# KN_ATx32.net
KiCad netlist of a schematic drawn in Altium Designer
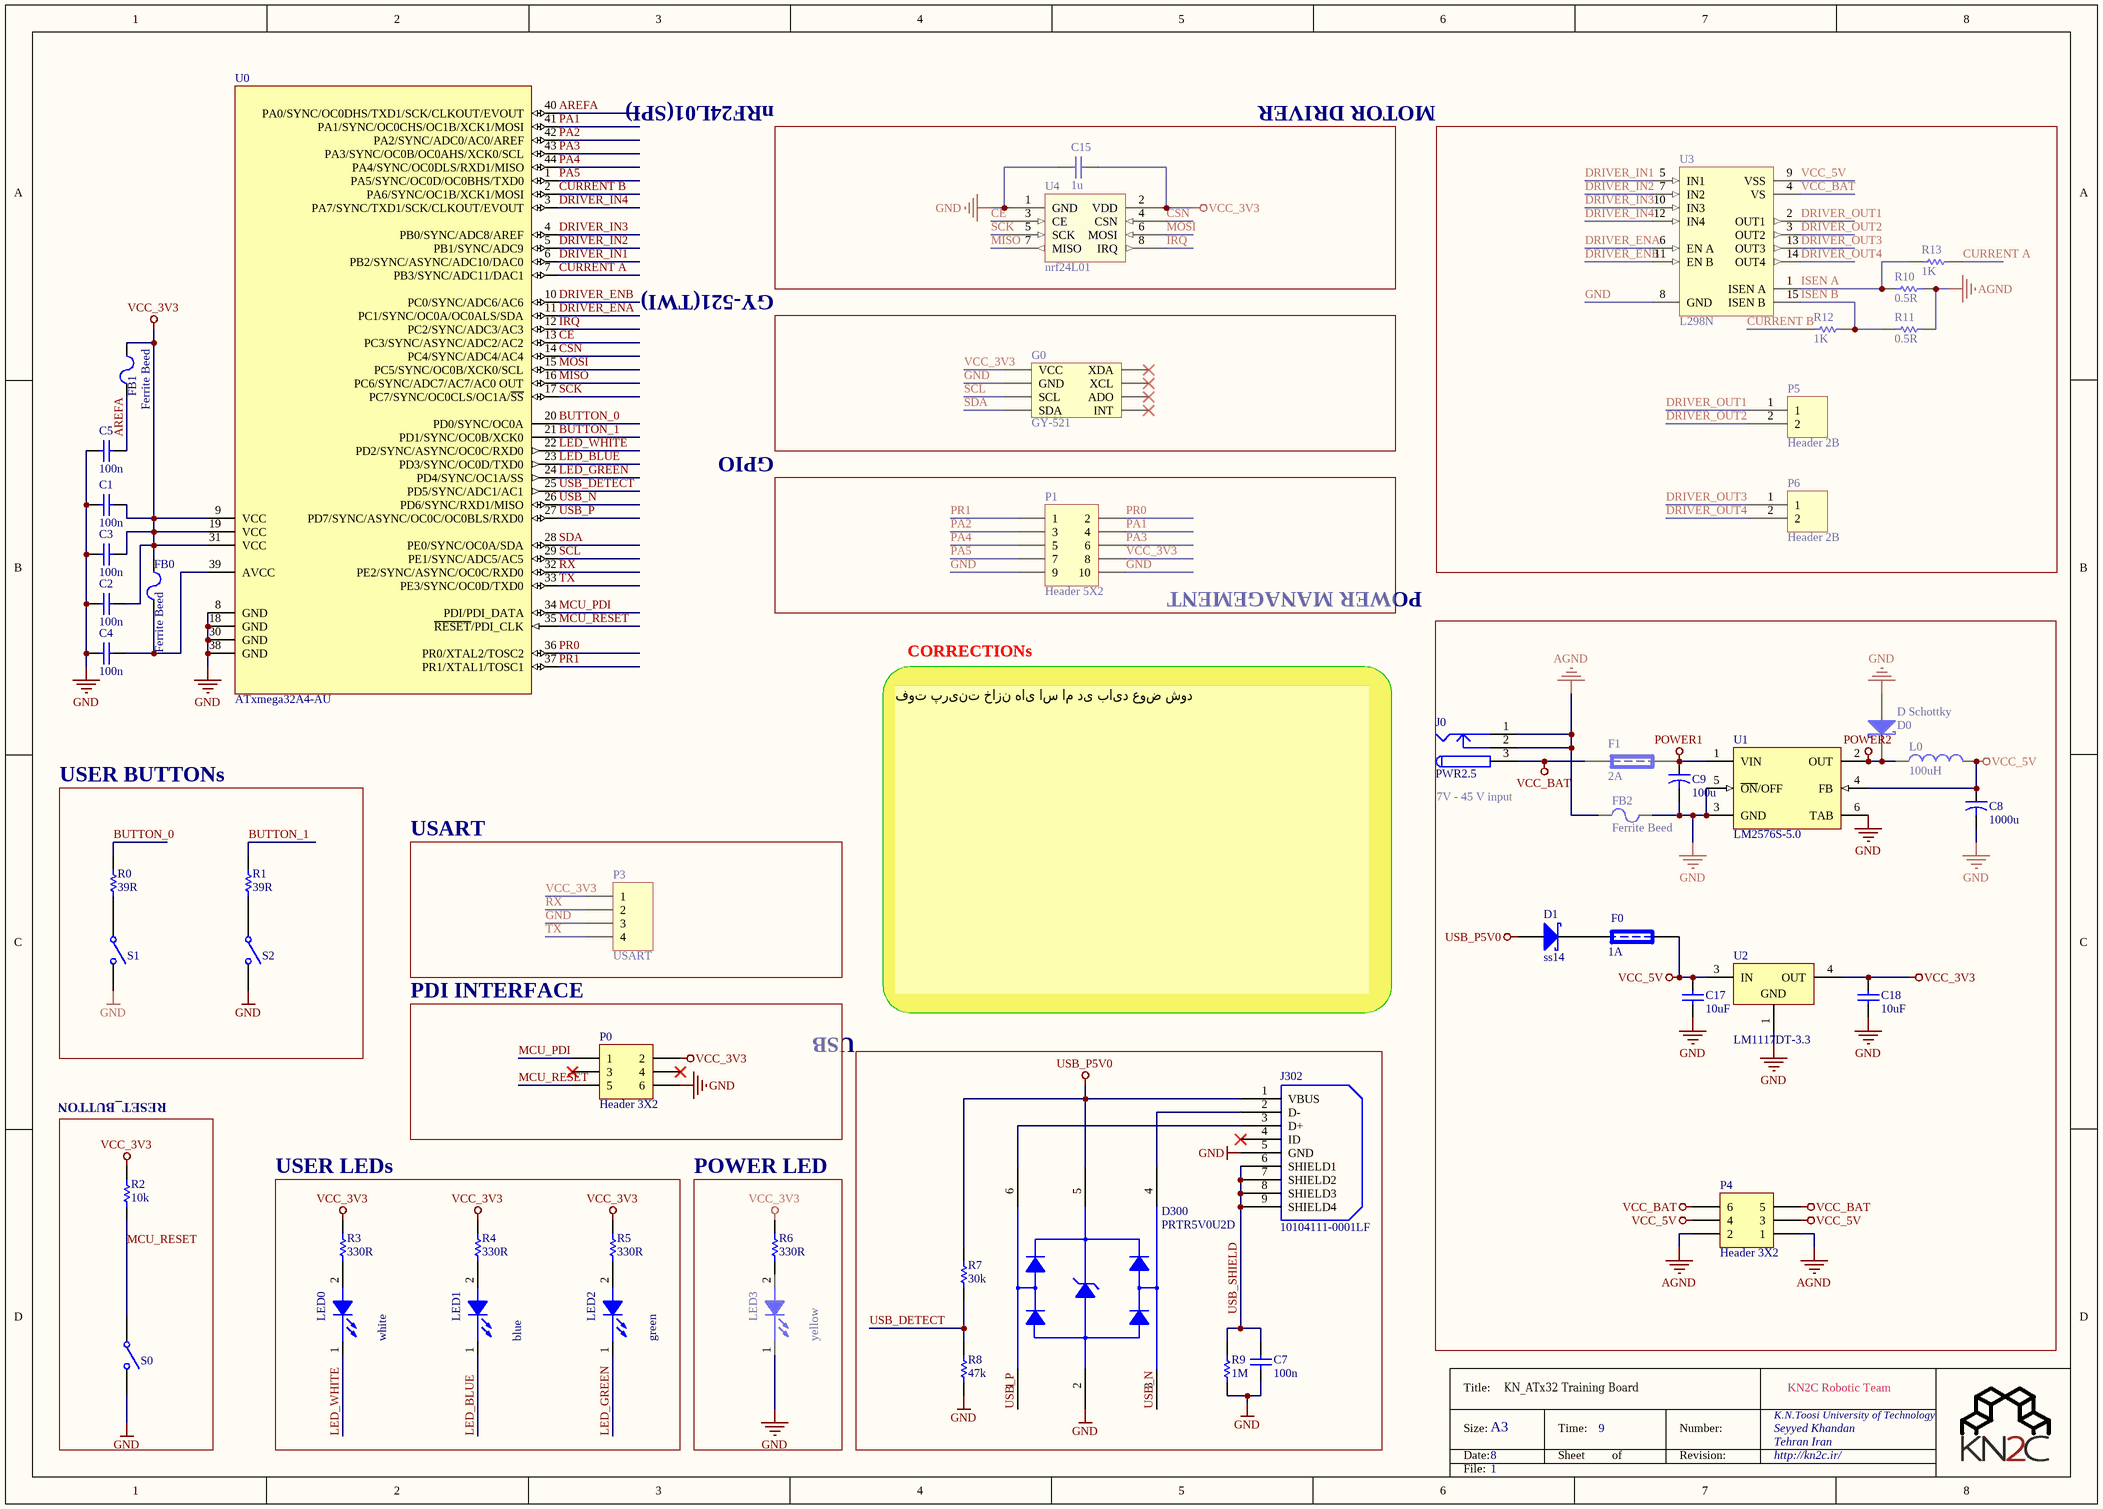
[diagram p0: KN_ATx32.SchDoc]

(export (version "E")
  (design (tool "Eeschema 10.0.6"))
  (components
    (comp (ref "C1")
      (value "100n")
      (footprint "6-0805_N")
      (description "Capacitor")
      (fields (field (name "PUBLISHER") "Altium Limited"))
      (libsource (lib "Miscellaneous Devices") (part "Cap"))
    )
    (comp (ref "C2")
      (value "100n")
      (footprint "6-0805_N")
      (description "Capacitor")
      (fields (field (name "PUBLISHER") "Altium Limited"))
      (libsource (lib "Miscellaneous Devices") (part "Cap"))
    )
    (comp (ref "C3")
      (value "100n")
      (footprint "6-0805_N")
      (description "Capacitor")
      (fields (field (name "PUBLISHER") "Altium Limited"))
      (libsource (lib "Miscellaneous Devices") (part "Cap"))
    )
    (comp (ref "C4")
      (value "100n")
      (footprint "6-0805_N")
      (description "Capacitor")
      (fields (field (name "PUBLISHER") "Altium Limited"))
      (libsource (lib "Miscellaneous Devices") (part "Cap"))
    )
    (comp (ref "C5")
      (value "100n")
      (footprint "6-0805_N")
      (description "Capacitor")
      (fields (field (name "PUBLISHER") "Altium Limited"))
      (libsource (lib "Miscellaneous Devices") (part "Cap"))
    )
    (comp (ref "C7")
      (value "100n")
      (footprint "6-0805_N")
      (description "Capacitor")
      (fields (field (name "PUBLISHER") "Altium Limited"))
      (libsource (lib "Miscellaneous Devices") (part "Cap"))
    )
    (comp (ref "C8")
      (value "1000u")
      (footprint "AP1-00122")
      (description "Capacitor")
      (fields (field (name "PUBLISHER") "Altium Limited"))
      (libsource (lib "KN2CLib") (part "Cap_El_200V"))
    )
    (comp (ref "C9")
      (value "100u")
      (footprint "AP1-00122")
      (description "Capacitor")
      (fields (field (name "PUBLISHER") "Altium Limited"))
      (libsource (lib "KN2CLib") (part "Cap_El_200V"))
    )
    (comp (ref "C15")
      (value "1u")
      (footprint "6-0805_N")
      (description "Capacitor")
      (fields (field (name "PUBLISHER") "Altium Limited"))
      (libsource (lib "Miscellaneous Devices") (part "Cap"))
    )
    (comp (ref "C17")
      (value "10uF")
      (footprint "2012[0805]")
      (description "Capacitor")
      (fields (field (name "PUBLISHER") "Altium Limited"))
      (libsource (lib "KN2CLib") (part "Cap_UP"))
    )
    (comp (ref "C18")
      (value "10uF")
      (footprint "2012[0805]")
      (description "Capacitor")
      (fields (field (name "PUBLISHER") "Altium Limited"))
      (libsource (lib "KN2CLib") (part "Cap_UP"))
    )
    (comp (ref "D0")
      (value "D Schottky")
      (footprint "us1m")
      (description "Schottky Diode")
      (fields (field (name "PUBLISHER") "Altium Limited"))
      (libsource (lib "Miscellaneous Devices") (part "D Schottky"))
    )
    (comp (ref "D1")
      (value "ss14")
      (footprint "US1m")
      (description "Schottky Diode")
      (fields (field (name "PUBLISHER") "Altium Limited"))
      (libsource (lib "Miscellaneous Devices") (part "D Schottky"))
    )
    (comp (ref "D300")
      (value "PRTR5V0U2D")
      (footprint "SOT457_N")
      (description "Double rail-to-rail USB ESD protection diode")
      (fields (field (name "MANUFACTURER") "Philips") (field (name "MPN") "PRTR5V0U2X"))
      (libsource (lib "KN2CLib") (part "PRTR5V0U2D"))
    )
    (comp (ref "F0")
      (value "1A")
      (footprint "1206")
      (description "Fuse")
      (fields (field (name "PUBLISHER") "Altium Limited"))
      (libsource (lib "KN2CLib") (part "Fuse"))
    )
    (comp (ref "F1")
      (value "2A")
      (footprint "1206")
      (description "Fuse")
      (fields (field (name "PUBLISHER") "Altium Limited"))
      (libsource (lib "KN2CLib") (part "Fuse"))
    )
    (comp (ref "FB0")
      (value "Ferrite Beed")
      (footprint "2012[0805]")
      (fields (field (name "PUBLISHER") "Altium Limited"))
      (libsource (lib "KN2CLib") (part "Ferrite Beed"))
    )
    (comp (ref "FB1")
      (value "Ferrite Beed")
      (footprint "2012[0805]")
      (fields (field (name "PUBLISHER") "Altium Limited"))
      (libsource (lib "KN2CLib") (part "Ferrite Beed"))
    )
    (comp (ref "FB2")
      (value "Ferrite Beed")
      (footprint "AXIAL-0.3")
      (fields (field (name "PUBLISHER") "Altium Limited"))
      (libsource (lib "KN2CLib") (part "Ferrite Beed"))
    )
    (comp (ref "G0") (value "GY-521") (footprint "GY-521") (libsource (lib "KN2CLib") (part "GY-521")))
    (comp (ref "J0")
      (value "PWR2.5")
      (footprint "CHARGER2")
      (description "Low Voltage Power Supply Connector")
      (fields (field (name "PUBLISHER") "Altium Limited"))
      (libsource (lib "KN2CLib") (part "PWR2.5"))
    )
    (comp (ref "J302")
      (value "10104111-0001LF")
      (footprint "AP8-00852")
      (description "Micro USB AB Connector")
      (fields (field (name "MANUFACTURER") "FCI") (field (name "Comment") "USB_AB"))
      (libsource (lib "KN2CLib") (part "USB_AB"))
    )
    (comp (ref "L0")
      (value "100uH")
      (footprint "INDUCTOR_SMD")
      (description "Inductor")
      (fields (field (name "PUBLISHER") "Altium Limited"))
      (libsource (lib "KN2CLib") (part "Inductor"))
    )
    (comp (ref "LED0")
      (value "white")
      (footprint "6-0805_N")
      (description "LED, Yellow, Wave length=591nm, SMD 0805, ±70°")
      (fields (field (name "MANUFACTURER") "Everlight") (field (name "MPN") "17-21UYC/S530-A3/TR8"))
      (libsource (lib "AltiumDbLib") (part "LED_12"))
    )
    (comp (ref "LED1")
      (value "blue")
      (footprint "6-0805_N")
      (description "LED, Yellow, Wave length=591nm, SMD 0805, ±70°")
      (fields (field (name "MANUFACTURER") "Everlight") (field (name "MPN") "17-21UYC/S530-A3/TR8"))
      (libsource (lib "AltiumDbLib") (part "LED_12"))
    )
    (comp (ref "LED2")
      (value "green")
      (footprint "6-0805_N")
      (description "LED, Yellow, Wave length=591nm, SMD 0805, ±70°")
      (fields (field (name "MANUFACTURER") "Everlight") (field (name "MPN") "17-21UYC/S530-A3/TR8"))
      (libsource (lib "AltiumDbLib") (part "LED_12"))
    )
    (comp (ref "LED3")
      (value "yellow")
      (footprint "6-0805_N")
      (description "LED, Yellow, Wave length=591nm, SMD 0805, ±70°")
      (fields (field (name "MANUFACTURER") "Everlight") (field (name "MPN") "17-21UYC/S530-A3/TR8"))
      (libsource (lib "AltiumDbLib") (part "LED_12"))
    )
    (comp (ref "P0")
      (value "Header 3X2")
      (footprint "HDRBOX2X3")
      (description "Header, 3-Pin, Dual row")
      (fields (field (name "PUBLISHER") "Altium Limited"))
      (libsource (lib "KN2CLib") (part "Header 3X2"))
    )
    (comp (ref "P1")
      (value "Header 5X2")
      (footprint "HDR2X5")
      (description "Header, 5-Pin, Dual row")
      (fields (field (name "PUBLISHER") "Altium Limited"))
      (libsource (lib "KN2CLib") (part "Header 5X2"))
    )
    (comp (ref "P3")
      (value "USART")
      (footprint "HDR1X4")
      (description "Header, 4-Pin")
      (fields (field (name "PUBLISHER") "Altium Limited"))
      (libsource (lib "Miscellaneous Connectors") (part "Header 4"))
    )
    (comp (ref "P4")
      (value "Header 3X2")
      (footprint "HDR2X3")
      (description "Header, 3-Pin, Dual row")
      (fields (field (name "PUBLISHER") "Altium Limited"))
      (libsource (lib "") (part "Header 3X2_1"))
    )
    (comp (ref "P5") (value "Header 2B") (footprint "CON2") (libsource (lib "KN2CLib") (part "Header 2B")))
    (comp (ref "P6") (value "Header 2B") (footprint "CON2") (libsource (lib "KN2CLib") (part "Header 2B")))
    (comp (ref "R0")
      (value "39R")
      (footprint "2012[0805]")
      (description "Semiconductor Resistor")
      (fields (field (name "PUBLISHER") "Altium Limited"))
      (libsource (lib "KN2CLib") (part "Res"))
    )
    (comp (ref "R1")
      (value "39R")
      (footprint "2012[0805]")
      (description "Semiconductor Resistor")
      (fields (field (name "PUBLISHER") "Altium Limited"))
      (libsource (lib "KN2CLib") (part "Res"))
    )
    (comp (ref "R2")
      (value "10k")
      (footprint "2012[0805]")
      (description "Semiconductor Resistor")
      (fields (field (name "PUBLISHER") "Altium Limited"))
      (libsource (lib "KN2CLib") (part "Res"))
    )
    (comp (ref "R3")
      (value "330R")
      (footprint "2012[0805]")
      (description "Semiconductor Resistor")
      (fields (field (name "PUBLISHER") "Altium Limited"))
      (libsource (lib "KN2CLib") (part "Res"))
    )
    (comp (ref "R4")
      (value "330R")
      (footprint "2012[0805]")
      (description "Semiconductor Resistor")
      (fields (field (name "PUBLISHER") "Altium Limited"))
      (libsource (lib "KN2CLib") (part "Res"))
    )
    (comp (ref "R5")
      (value "330R")
      (footprint "2012[0805]")
      (description "Semiconductor Resistor")
      (fields (field (name "PUBLISHER") "Altium Limited"))
      (libsource (lib "KN2CLib") (part "Res"))
    )
    (comp (ref "R6")
      (value "330R")
      (footprint "2012[0805]")
      (description "Semiconductor Resistor")
      (fields (field (name "PUBLISHER") "Altium Limited"))
      (libsource (lib "KN2CLib") (part "Res"))
    )
    (comp (ref "R7")
      (value "30k")
      (footprint "2012[0805]")
      (description "Semiconductor Resistor")
      (fields (field (name "PUBLISHER") "Altium Limited"))
      (libsource (lib "KN2CLib") (part "Res"))
    )
    (comp (ref "R8")
      (value "47k")
      (footprint "2012[0805]")
      (description "Semiconductor Resistor")
      (fields (field (name "PUBLISHER") "Altium Limited"))
      (libsource (lib "KN2CLib") (part "Res"))
    )
    (comp (ref "R9")
      (value "1M")
      (footprint "2012[0805]")
      (description "Semiconductor Resistor")
      (fields (field (name "PUBLISHER") "Altium Limited"))
      (libsource (lib "KN2CLib") (part "Res"))
    )
    (comp (ref "R10")
      (value "0.5R")
      (footprint "6332[2512]")
      (description "Semiconductor Resistor")
      (fields (field (name "PUBLISHER") "Altium Limited"))
      (libsource (lib "KN2CLib") (part "Res"))
    )
    (comp (ref "R11")
      (value "0.5R")
      (footprint "6332[2512]")
      (description "Semiconductor Resistor")
      (fields (field (name "PUBLISHER") "Altium Limited"))
      (libsource (lib "KN2CLib") (part "Res"))
    )
    (comp (ref "R12")
      (value "1K")
      (footprint "2012[0805]")
      (description "Semiconductor Resistor")
      (fields (field (name "PUBLISHER") "Altium Limited"))
      (libsource (lib "KN2CLib") (part "Res"))
    )
    (comp (ref "R13")
      (value "1K")
      (footprint "2012[0805]")
      (description "Semiconductor Resistor")
      (fields (field (name "PUBLISHER") "Altium Limited"))
      (libsource (lib "KN2CLib") (part "Res"))
    )
    (comp (ref "S0")
      (value "SW-SPST")
      (footprint "pushbutton_smd")
      (description "Single-Pole, Single-Throw Switch")
      (fields (field (name "PUBLISHER") "Altium Limited"))
      (libsource (lib "KN2CLib") (part "SW-SPST"))
    )
    (comp (ref "S1")
      (value "SW-SPST")
      (footprint "pushbutton_smd")
      (description "Single-Pole, Single-Throw Switch")
      (fields (field (name "PUBLISHER") "Altium Limited"))
      (libsource (lib "KN2CLib") (part "SW-SPST"))
    )
    (comp (ref "S2")
      (value "SW-SPST")
      (footprint "pushbutton_smd")
      (description "Single-Pole, Single-Throw Switch")
      (fields (field (name "PUBLISHER") "Altium Limited"))
      (libsource (lib "KN2CLib") (part "SW-SPST"))
    )
    (comp (ref "U0")
      (value "ATxmega32A4-AU")
      (footprint "44A_N")
      (fields (field (name "PUBLISHER") "Altium Limited"))
      (libsource (lib "Atmel Microcontroller 8-16-Bit AVR XMEGA") (part "ATxmega32A4-AU"))
    )
    (comp (ref "U1")
      (value "LM2576S-5.0")
      (footprint "TS5B_N")
      (description "SIMPLE SWITCHER® 3A Step-Down Voltage Regulator, 5-pin TO-263")
      (fields
        (field (name "MANUFACTURER") "National Semiconductor")
        (field (name "PUBLISHER") "Altium Limited")
      )
      (libsource (lib "KN2CLib") (part "LM2576S-5.0"))
    )
    (comp (ref "U2")
      (value "LM1117DT-3.3")
      (footprint "SOT223")
      (description "800mA Low-Dropout Linear Regulator, 3-pin TO-252")
      (fields
        (field (name "MANUFACTURER") "National Semiconductor")
        (field (name "PUBLISHER") "Altium Limited")
      )
      (libsource (lib "NSC LDO") (part "LM1117DT-3.3"))
    )
    (comp (ref "U3")
      (value "L298N")
      (footprint "Multiwatt15V")
      (description "Dual Full Bridge Driver")
      (fields (field (name "PUBLISHER") "Altium Limited"))
      (libsource (lib "ST Interface DC Motor Controller") (part "L298N"))
    )
    (comp (ref "U4") (value "nrf24L01") (footprint "NRF24L01") (libsource (lib "KN2CLib") (part "nrf24L01")))
  )
  (nets
    (net (code "1") (name "/AREFA") (class "Default")
      (node (ref "C5") (pin "2") (pinfunction "2_2") (pintype "passive"))
      (node (ref "FB1") (pin "1") (pinfunction "1_1") (pintype "passive"))
      (node (ref "U0") (pin "40") (pinfunction "PA0/SYNC/OC0DHS/TXD1/SCK/CLKOUT/EVOUT_40") (pintype "bidirectional"))
    )
    (net (code "2") (name "/BUTTON_0") (class "Default")
      (node (ref "R0") (pin "2") (pinfunction "2_2") (pintype "passive"))
      (node (ref "U0") (pin "20") (pinfunction "PD0/SYNC/OC0A_20") (pintype "open_emitter"))
    )
    (net (code "3") (name "/BUTTON_1") (class "Default")
      (node (ref "R1") (pin "2") (pinfunction "2_2") (pintype "passive"))
      (node (ref "U0") (pin "21") (pinfunction "PD1/SYNC/OC0B/XCK0_21") (pintype "open_emitter"))
    )
    (net (code "4") (name "/CE") (class "Default")
      (node (ref "U0") (pin "13") (pinfunction "PC3/SYNC/ASYNC/ADC2/AC2_13") (pintype "bidirectional"))
      (node (ref "U4") (pin "3") (pinfunction "CE_3") (pintype "input"))
    )
    (net (code "5") (name "/CSN") (class "Default")
      (node (ref "U0") (pin "14") (pinfunction "PC4/SYNC/ADC4/AC4_14") (pintype "bidirectional"))
      (node (ref "U4") (pin "4") (pinfunction "CSN_4") (pintype "input"))
    )
    (net (code "6") (name "/CURRENT A") (class "Default")
      (node (ref "R13") (pin "2") (pinfunction "2_2") (pintype "passive"))
      (node (ref "U0") (pin "7") (pinfunction "PB3/SYNC/ADC11/DAC1_7") (pintype "bidirectional"))
    )
    (net (code "7") (name "/CURRENT B") (class "Default")
      (node (ref "R12") (pin "1") (pinfunction "1_1") (pintype "passive"))
      (node (ref "U0") (pin "2") (pinfunction "PA6/SYNC/OC1B/XCK1/MOSI_2") (pintype "bidirectional"))
    )
    (net (code "8") (name "/DRIVER_ENA") (class "Default")
      (node (ref "U0") (pin "11") (pinfunction "PC1/SYNC/OC0A/OC0ALS/SDA_11") (pintype "bidirectional"))
      (node (ref "U3") (pin "6") (pinfunction "EN_A_6") (pintype "input"))
    )
    (net (code "9") (name "/DRIVER_ENB") (class "Default")
      (node (ref "U0") (pin "10") (pinfunction "PC0/SYNC/ADC6/AC6_10") (pintype "bidirectional"))
      (node (ref "U3") (pin "11") (pinfunction "EN_B_11") (pintype "input"))
    )
    (net (code "10") (name "/DRIVER_IN1") (class "Default")
      (node (ref "U0") (pin "6") (pinfunction "PB2/SYNC/ASYNC/ADC10/DAC0_6") (pintype "bidirectional"))
      (node (ref "U3") (pin "5") (pinfunction "IN1_5") (pintype "input"))
    )
    (net (code "11") (name "/DRIVER_IN2") (class "Default")
      (node (ref "U0") (pin "5") (pinfunction "PB1/SYNC/ADC9_5") (pintype "bidirectional"))
      (node (ref "U3") (pin "7") (pinfunction "IN2_7") (pintype "input"))
    )
    (net (code "12") (name "/DRIVER_IN3") (class "Default")
      (node (ref "U0") (pin "4") (pinfunction "PB0/SYNC/ADC8/AREF_4") (pintype "bidirectional"))
      (node (ref "U3") (pin "10") (pinfunction "IN3_10") (pintype "input"))
    )
    (net (code "13") (name "/DRIVER_IN4") (class "Default")
      (node (ref "U0") (pin "3") (pinfunction "PA7/SYNC/TXD1/SCK/CLKOUT/EVOUT_3") (pintype "bidirectional"))
      (node (ref "U3") (pin "12") (pinfunction "IN4_12") (pintype "input"))
    )
    (net (code "14") (name "/DRIVER_OUT1") (class "Default")
      (node (ref "P5") (pin "1") (pinfunction "1_1") (pintype "passive"))
      (node (ref "U3") (pin "2") (pinfunction "OUT1_2") (pintype "output"))
    )
    (net (code "15") (name "/DRIVER_OUT2") (class "Default")
      (node (ref "P5") (pin "2") (pinfunction "2_2") (pintype "passive"))
      (node (ref "U3") (pin "3") (pinfunction "OUT2_3") (pintype "output"))
    )
    (net (code "16") (name "/DRIVER_OUT3") (class "Default")
      (node (ref "P6") (pin "1") (pinfunction "1_1") (pintype "passive"))
      (node (ref "U3") (pin "13") (pinfunction "OUT3_13") (pintype "output"))
    )
    (net (code "17") (name "/DRIVER_OUT4") (class "Default")
      (node (ref "P6") (pin "2") (pinfunction "2_2") (pintype "passive"))
      (node (ref "U3") (pin "14") (pinfunction "OUT4_14") (pintype "output"))
    )
    (net (code "18") (name "/IRQ") (class "Default")
      (node (ref "U0") (pin "12") (pinfunction "PC2/SYNC/ADC3/AC3_12") (pintype "bidirectional"))
      (node (ref "U4") (pin "8") (pinfunction "IRQ_8") (pintype "output"))
    )
    (net (code "19") (name "/ISEN A") (class "Default")
      (node (ref "R10") (pin "1") (pinfunction "1_1") (pintype "passive"))
      (node (ref "R13") (pin "1") (pinfunction "1_1") (pintype "passive"))
      (node (ref "U3") (pin "1") (pinfunction "ISEN_A_1") (pintype "passive"))
    )
    (net (code "20") (name "/ISEN B") (class "Default")
      (node (ref "R11") (pin "1") (pinfunction "1_1") (pintype "passive"))
      (node (ref "R12") (pin "2") (pinfunction "2_2") (pintype "passive"))
      (node (ref "U3") (pin "15") (pinfunction "ISEN_B_15") (pintype "passive"))
    )
    (net (code "21") (name "/LED_BLUE") (class "Default")
      (node (ref "LED1") (pin "1") (pinfunction "CATHODE_1") (pintype "passive"))
      (node (ref "U0") (pin "23") (pinfunction "PD3/SYNC/OC0D/TXD0_23") (pintype "output"))
    )
    (net (code "22") (name "/LED_GREEN") (class "Default")
      (node (ref "LED2") (pin "1") (pinfunction "CATHODE_1") (pintype "passive"))
      (node (ref "U0") (pin "24") (pinfunction "PD4/SYNC/OC1A/SS_24") (pintype "output"))
    )
    (net (code "23") (name "/LED_WHITE") (class "Default")
      (node (ref "LED0") (pin "1") (pinfunction "CATHODE_1") (pintype "passive"))
      (node (ref "U0") (pin "22") (pinfunction "PD2/SYNC/ASYNC/OC0C/RXD0_22") (pintype "output"))
    )
    (net (code "24") (name "/MCU_PDI") (class "Default")
      (node (ref "P0") (pin "1") (pinfunction "1_1") (pintype "passive"))
      (node (ref "U0") (pin "34") (pinfunction "PDI/PDI_DATA_34") (pintype "bidirectional"))
    )
    (net (code "25") (name "/MCU_RESET") (class "Default")
      (node (ref "P0") (pin "5") (pinfunction "5_5") (pintype "passive"))
      (node (ref "R2") (pin "1") (pinfunction "1_1") (pintype "passive"))
      (node (ref "S0") (pin "1") (pinfunction "COMMON_1") (pintype "passive"))
      (node (ref "U0") (pin "35") (pinfunction "~{RESET}/PDI_CLK_35") (pintype "input"))
    )
    (net (code "26") (name "/MISO") (class "Default")
      (node (ref "U0") (pin "16") (pinfunction "PC6/SYNC/ADC7/AC7/AC0_OUT_16") (pintype "bidirectional"))
      (node (ref "U4") (pin "7") (pinfunction "MISO_7") (pintype "output"))
    )
    (net (code "27") (name "/MOSI") (class "Default")
      (node (ref "U0") (pin "15") (pinfunction "PC5/SYNC/OC0B/XCK0/SCL_15") (pintype "bidirectional"))
      (node (ref "U4") (pin "6") (pinfunction "MOSI_6") (pintype "input"))
    )
    (net (code "28") (name "/PA1") (class "Default")
      (node (ref "P1") (pin "4") (pinfunction "4_4") (pintype "passive"))
      (node (ref "U0") (pin "41") (pinfunction "PA1/SYNC/OC0CHS/OC1B/XCK1/MOSI_41") (pintype "bidirectional"))
    )
    (net (code "29") (name "/PA2") (class "Default")
      (node (ref "P1") (pin "3") (pinfunction "3_3") (pintype "passive"))
      (node (ref "U0") (pin "42") (pinfunction "PA2/SYNC/ADC0/AC0/AREF_42") (pintype "bidirectional"))
    )
    (net (code "30") (name "/PA3") (class "Default")
      (node (ref "P1") (pin "6") (pinfunction "6_6") (pintype "passive"))
      (node (ref "U0") (pin "43") (pinfunction "PA3/SYNC/OC0B/OC0AHS/XCK0/SCL_43") (pintype "bidirectional"))
    )
    (net (code "31") (name "/PA4") (class "Default")
      (node (ref "P1") (pin "5") (pinfunction "5_5") (pintype "passive"))
      (node (ref "U0") (pin "44") (pinfunction "PA4/SYNC/OC0DLS/RXD1/MISO_44") (pintype "bidirectional"))
    )
    (net (code "32") (name "/PA5") (class "Default")
      (node (ref "P1") (pin "7") (pinfunction "7_7") (pintype "passive"))
      (node (ref "U0") (pin "1") (pinfunction "PA5/SYNC/OC0D/OC0BHS/TXD0_1") (pintype "bidirectional"))
    )
    (net (code "33") (name "/PR0") (class "Default")
      (node (ref "P1") (pin "2") (pinfunction "2_2") (pintype "passive"))
      (node (ref "U0") (pin "36") (pinfunction "PR0/XTAL2/TOSC2_36") (pintype "bidirectional"))
    )
    (net (code "34") (name "/PR1") (class "Default")
      (node (ref "P1") (pin "1") (pinfunction "1_1") (pintype "passive"))
      (node (ref "U0") (pin "37") (pinfunction "PR1/XTAL1/TOSC1_37") (pintype "bidirectional"))
    )
    (net (code "35") (name "/RX") (class "Default")
      (node (ref "P3") (pin "2") (pinfunction "2_2") (pintype "passive"))
      (node (ref "U0") (pin "32") (pinfunction "PE2/SYNC/ASYNC/OC0C/RXD0_32") (pintype "bidirectional"))
    )
    (net (code "36") (name "/SCK") (class "Default")
      (node (ref "U0") (pin "17") (pinfunction "PC7/SYNC/OC0CLS/OC1A/~{SS}_17") (pintype "bidirectional"))
      (node (ref "U4") (pin "5") (pinfunction "SCK_5") (pintype "input"))
    )
    (net (code "37") (name "/SCL") (class "Default")
      (node (ref "G0") (pin "3") (pinfunction "SCL_3") (pintype "passive"))
      (node (ref "U0") (pin "29") (pinfunction "PE1/SYNC/ADC5/AC5_29") (pintype "bidirectional"))
    )
    (net (code "38") (name "/SDA") (class "Default")
      (node (ref "G0") (pin "4") (pinfunction "SDA_4") (pintype "passive"))
      (node (ref "U0") (pin "28") (pinfunction "PE0/SYNC/OC0A/SDA_28") (pintype "bidirectional"))
    )
    (net (code "39") (name "/TX") (class "Default")
      (node (ref "P3") (pin "4") (pinfunction "4_4") (pintype "passive"))
      (node (ref "U0") (pin "33") (pinfunction "PE3/SYNC/OC0D/TXD0_33") (pintype "bidirectional"))
    )
    (net (code "40") (name "/USB_DETECT") (class "Default")
      (node (ref "R7") (pin "1") (pinfunction "1_1") (pintype "passive"))
      (node (ref "R8") (pin "2") (pinfunction "2_2") (pintype "passive"))
      (node (ref "U0") (pin "25") (pinfunction "PD5/SYNC/ADC1/AC1_25") (pintype "output"))
    )
    (net (code "41") (name "/USB_N") (class "Default")
      (node (ref "D300") (pin "3") (pinfunction "I/O2_3") (pintype "passive"))
      (node (ref "U0") (pin "26") (pinfunction "PD6/SYNC/RXD1/MISO_26") (pintype "bidirectional"))
    )
    (net (code "42") (name "/USB_P") (class "Default")
      (node (ref "D300") (pin "1") (pinfunction "I/O_1_1") (pintype "passive"))
      (node (ref "U0") (pin "27") (pinfunction "PD7/SYNC/ASYNC/OC0C/OC0BLS/RXD0_27") (pintype "bidirectional"))
    )
    (net (code "43") (name "/USB_SHIELD") (class "Default")
      (node (ref "C7") (pin "2") (pinfunction "2_2") (pintype "passive"))
      (node (ref "J302") (pin "6") (pinfunction "SHIELD1_6") (pintype "passive"))
      (node (ref "J302") (pin "7") (pinfunction "SHIELD2_7") (pintype "passive"))
      (node (ref "J302") (pin "8") (pinfunction "SHIELD3_8") (pintype "passive"))
      (node (ref "J302") (pin "9") (pinfunction "SHIELD4_9") (pintype "passive"))
      (node (ref "R9") (pin "2") (pinfunction "2_2") (pintype "passive"))
    )
    (net (code "44") (name "AGND") (class "Default")
      (node (ref "FB2") (pin "2") (pinfunction "2_2") (pintype "passive"))
      (node (ref "J0") (pin "1") (pinfunction "1_1") (pintype "passive"))
      (node (ref "J0") (pin "2") (pinfunction "2_2") (pintype "passive"))
      (node (ref "P4") (pin "1") (pinfunction "1_1") (pintype "passive"))
      (node (ref "P4") (pin "2") (pinfunction "2_2") (pintype "passive"))
      (node (ref "R10") (pin "2") (pinfunction "2_2") (pintype "passive"))
      (node (ref "R11") (pin "2") (pinfunction "2_2") (pintype "passive"))
    )
    (net (code "45") (name "GND") (class "Default")
      (node (ref "C1") (pin "1") (pinfunction "1_1") (pintype "passive"))
      (node (ref "C15") (pin "1") (pinfunction "1_1") (pintype "passive"))
      (node (ref "C17") (pin "1") (pinfunction "1_1") (pintype "passive"))
      (node (ref "C18") (pin "1") (pinfunction "1_1") (pintype "passive"))
      (node (ref "C2") (pin "1") (pinfunction "1_1") (pintype "passive"))
      (node (ref "C3") (pin "1") (pinfunction "1_1") (pintype "passive"))
      (node (ref "C4") (pin "1") (pinfunction "1_1") (pintype "passive"))
      (node (ref "C5") (pin "1") (pinfunction "1_1") (pintype "passive"))
      (node (ref "C7") (pin "1") (pinfunction "1_1") (pintype "passive"))
      (node (ref "C8") (pin "2") (pinfunction "2_2") (pintype "passive"))
      (node (ref "C9") (pin "2") (pinfunction "2_2") (pintype "passive"))
      (node (ref "D0") (pin "1") (pinfunction "A_1") (pintype "passive"))
      (node (ref "D300") (pin "2") (pinfunction "GND_2") (pintype "passive"))
      (node (ref "FB2") (pin "1") (pinfunction "1_1") (pintype "passive"))
      (node (ref "G0") (pin "2") (pinfunction "GND_2") (pintype "passive"))
      (node (ref "J302") (pin "5") (pinfunction "GND_5") (pintype "passive"))
      (node (ref "LED3") (pin "1") (pinfunction "CATHODE_1") (pintype "passive"))
      (node (ref "P0") (pin "6") (pinfunction "6_6") (pintype "passive"))
      (node (ref "P1") (pin "10") (pinfunction "10_10") (pintype "passive"))
      (node (ref "P1") (pin "9") (pinfunction "9_9") (pintype "passive"))
      (node (ref "P3") (pin "3") (pinfunction "3_3") (pintype "passive"))
      (node (ref "R8") (pin "1") (pinfunction "1_1") (pintype "passive"))
      (node (ref "R9") (pin "1") (pinfunction "1_1") (pintype "passive"))
      (node (ref "S0") (pin "2") (pinfunction "NO_2") (pintype "passive"))
      (node (ref "S1") (pin "2") (pinfunction "NO_2") (pintype "passive"))
      (node (ref "S2") (pin "2") (pinfunction "NO_2") (pintype "passive"))
      (node (ref "U0") (pin "18") (pinfunction "GND_18") (pintype "power_in"))
      (node (ref "U0") (pin "30") (pinfunction "GND_30") (pintype "power_in"))
      (node (ref "U0") (pin "38") (pinfunction "GND_38") (pintype "power_in"))
      (node (ref "U0") (pin "8") (pinfunction "GND_8") (pintype "power_in"))
      (node (ref "U1") (pin "3") (pinfunction "GND_3") (pintype "power_in"))
      (node (ref "U1") (pin "5") (pinfunction "~{ON}/OFF_5") (pintype "input"))
      (node (ref "U1") (pin "6") (pinfunction "TAB_6") (pintype "power_in"))
      (node (ref "U2") (pin "1") (pinfunction "GND_1") (pintype "power_in"))
      (node (ref "U3") (pin "8") (pinfunction "GND_8") (pintype "power_in"))
      (node (ref "U4") (pin "1") (pinfunction "GND_1") (pintype "power_in"))
    )
    (net (code "46") (name "Net-(D1-K)") (class "Default")
      (node (ref "D1") (pin "2") (pinfunction "K_2") (pintype "passive"))
      (node (ref "F0") (pin "2") (pinfunction "2_2") (pintype "passive"))
    )
    (net (code "47") (name "Net-(D300-I{slash}O1)") (class "Default")
      (node (ref "D300") (pin "6") (pinfunction "I/O1_6") (pintype "passive"))
      (node (ref "J302") (pin "3") (pinfunction "D+_3") (pintype "passive"))
    )
    (net (code "48") (name "Net-(J302-D-)") (class "Default")
      (node (ref "D300") (pin "4") (pinfunction "I/O2_4") (pintype "passive"))
      (node (ref "J302") (pin "2") (pinfunction "D-_2") (pintype "passive"))
    )
    (net (code "49") (name "Net-(LED0-ANODE)") (class "Default")
      (node (ref "LED0") (pin "2") (pinfunction "ANODE_2") (pintype "passive"))
      (node (ref "R3") (pin "1") (pinfunction "1_1") (pintype "passive"))
    )
    (net (code "50") (name "Net-(LED1-ANODE)") (class "Default")
      (node (ref "LED1") (pin "2") (pinfunction "ANODE_2") (pintype "passive"))
      (node (ref "R4") (pin "1") (pinfunction "1_1") (pintype "passive"))
    )
    (net (code "51") (name "Net-(LED2-ANODE)") (class "Default")
      (node (ref "LED2") (pin "2") (pinfunction "ANODE_2") (pintype "passive"))
      (node (ref "R5") (pin "1") (pinfunction "1_1") (pintype "passive"))
    )
    (net (code "52") (name "Net-(LED3-ANODE)") (class "Default")
      (node (ref "LED3") (pin "2") (pinfunction "ANODE_2") (pintype "passive"))
      (node (ref "R6") (pin "1") (pinfunction "1_1") (pintype "passive"))
    )
    (net (code "53") (name "Net-(S1-COMMON)") (class "Default")
      (node (ref "R0") (pin "1") (pinfunction "1_1") (pintype "passive"))
      (node (ref "S1") (pin "1") (pinfunction "COMMON_1") (pintype "passive"))
    )
    (net (code "54") (name "Net-(S2-COMMON)") (class "Default")
      (node (ref "R1") (pin "1") (pinfunction "1_1") (pintype "passive"))
      (node (ref "S2") (pin "1") (pinfunction "COMMON_1") (pintype "passive"))
    )
    (net (code "55") (name "Net-(U0-AVCC)") (class "Default")
      (node (ref "C4") (pin "2") (pinfunction "2_2") (pintype "passive"))
      (node (ref "FB0") (pin "1") (pinfunction "1_1") (pintype "passive"))
      (node (ref "U0") (pin "39") (pinfunction "AVCC_39") (pintype "power_in"))
    )
    (net (code "56") (name "POWER1") (class "Default")
      (node (ref "C9") (pin "1") (pinfunction "1_1") (pintype "passive"))
      (node (ref "F1") (pin "2") (pinfunction "2_2") (pintype "passive"))
      (node (ref "U1") (pin "1") (pinfunction "VIN_1") (pintype "power_in"))
    )
    (net (code "57") (name "POWER2") (class "Default")
      (node (ref "D0") (pin "2") (pinfunction "K_2") (pintype "passive"))
      (node (ref "L0") (pin "1") (pinfunction "1_1") (pintype "passive"))
      (node (ref "U1") (pin "2") (pinfunction "OUT_2") (pintype "power_in"))
    )
    (net (code "58") (name "USB_P5V0") (class "Default")
      (node (ref "D1") (pin "1") (pinfunction "A_1") (pintype "passive"))
      (node (ref "D300") (pin "5") (pinfunction "VCC_5") (pintype "passive"))
      (node (ref "J302") (pin "1") (pinfunction "VBUS_1") (pintype "passive"))
      (node (ref "R7") (pin "2") (pinfunction "2_2") (pintype "passive"))
    )
    (net (code "59") (name "VCC_3V3") (class "Default")
      (node (ref "C1") (pin "2") (pinfunction "2_2") (pintype "passive"))
      (node (ref "C15") (pin "2") (pinfunction "2_2") (pintype "passive"))
      (node (ref "C18") (pin "2") (pinfunction "2_2") (pintype "passive"))
      (node (ref "C2") (pin "2") (pinfunction "2_2") (pintype "passive"))
      (node (ref "C3") (pin "2") (pinfunction "2_2") (pintype "passive"))
      (node (ref "FB0") (pin "2") (pinfunction "2_2") (pintype "passive"))
      (node (ref "FB1") (pin "2") (pinfunction "2_2") (pintype "passive"))
      (node (ref "G0") (pin "1") (pinfunction "VCC_1") (pintype "passive"))
      (node (ref "P0") (pin "2") (pinfunction "2_2") (pintype "passive"))
      (node (ref "P1") (pin "8") (pinfunction "8_8") (pintype "passive"))
      (node (ref "P3") (pin "1") (pinfunction "1_1") (pintype "passive"))
      (node (ref "R2") (pin "2") (pinfunction "2_2") (pintype "passive"))
      (node (ref "R3") (pin "2") (pinfunction "2_2") (pintype "passive"))
      (node (ref "R4") (pin "2") (pinfunction "2_2") (pintype "passive"))
      (node (ref "R5") (pin "2") (pinfunction "2_2") (pintype "passive"))
      (node (ref "R6") (pin "2") (pinfunction "2_2") (pintype "passive"))
      (node (ref "U0") (pin "19") (pinfunction "VCC_19") (pintype "power_in"))
      (node (ref "U0") (pin "31") (pinfunction "VCC_31") (pintype "power_in"))
      (node (ref "U0") (pin "9") (pinfunction "VCC_9") (pintype "power_in"))
      (node (ref "U2") (pin "4") (pinfunction "OUT_4") (pintype "power_in"))
      (node (ref "U4") (pin "2") (pinfunction "VDD_2") (pintype "power_in"))
    )
    (net (code "60") (name "VCC_5V") (class "Default")
      (node (ref "C17") (pin "2") (pinfunction "2_2") (pintype "passive"))
      (node (ref "C8") (pin "1") (pinfunction "1_1") (pintype "passive"))
      (node (ref "F0") (pin "1") (pinfunction "1_1") (pintype "passive"))
      (node (ref "L0") (pin "2") (pinfunction "2_2") (pintype "passive"))
      (node (ref "P4") (pin "3") (pinfunction "3_3") (pintype "passive"))
      (node (ref "P4") (pin "4") (pinfunction "4_4") (pintype "passive"))
      (node (ref "U1") (pin "4") (pinfunction "FB_4") (pintype "input"))
      (node (ref "U2") (pin "3") (pinfunction "IN_3") (pintype "power_in"))
      (node (ref "U3") (pin "9") (pinfunction "VSS_9") (pintype "power_in"))
    )
    (net (code "61") (name "VCC_BAT") (class "Default")
      (node (ref "F1") (pin "1") (pinfunction "1_1") (pintype "passive"))
      (node (ref "J0") (pin "3") (pinfunction "3_3") (pintype "passive"))
      (node (ref "P4") (pin "5") (pinfunction "5_5") (pintype "passive"))
      (node (ref "P4") (pin "6") (pinfunction "6_6") (pintype "passive"))
      (node (ref "U3") (pin "4") (pinfunction "VS_4") (pintype "power_in"))
    )
    (net (code "62") (name "unconnected-(G0-ADO-Pad7)") (class "Default")
      (node (ref "G0") (pin "7") (pinfunction "ADO_7") (pintype "passive+no_connect"))
    )
    (net (code "63") (name "unconnected-(G0-INT-Pad8)") (class "Default")
      (node (ref "G0") (pin "8") (pinfunction "INT_8") (pintype "passive+no_connect"))
    )
    (net (code "64") (name "unconnected-(G0-XCL-Pad6)") (class "Default")
      (node (ref "G0") (pin "6") (pinfunction "XCL_6") (pintype "passive+no_connect"))
    )
    (net (code "65") (name "unconnected-(G0-XDA-Pad5)") (class "Default")
      (node (ref "G0") (pin "5") (pinfunction "XDA_5") (pintype "passive+no_connect"))
    )
    (net (code "66") (name "unconnected-(J302-ID-Pad4)") (class "Default")
      (node (ref "J302") (pin "4") (pinfunction "ID_4") (pintype "passive+no_connect"))
    )
    (net (code "67") (name "unconnected-(P0-Pad3)") (class "Default")
      (node (ref "P0") (pin "3") (pinfunction "3_3") (pintype "passive+no_connect"))
    )
    (net (code "68") (name "unconnected-(P0-Pad4)") (class "Default")
      (node (ref "P0") (pin "4") (pinfunction "4_4") (pintype "passive+no_connect"))
    )
  )
)
